# 7_seg.net
KiCad netlist of a schematic drawn in Altium Designer
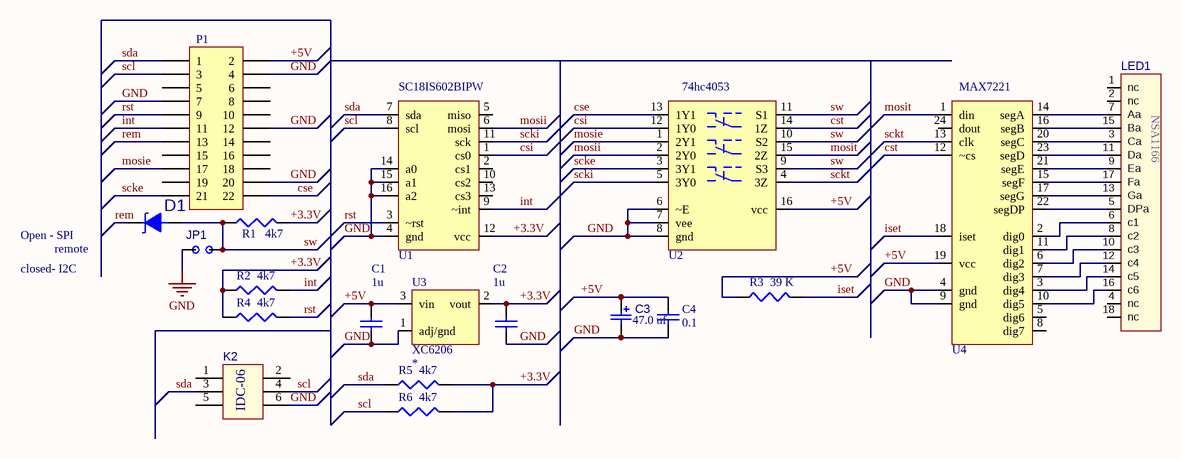
[diagram p0: 7_seg.SchDoc]

(export (version "E")
  (design (tool "Eeschema 10.0.6"))
  (components
    (comp (ref "C1")
      (value "1u")
      (footprint "SM0805")
      (description "Capacitor")
      (fields (field (name "Comment") "cap0805") (field (name "PUBLISHER") "Altium Limited"))
      (libsource (lib "alt2017") (part "cap0805"))
    )
    (comp (ref "C2")
      (value "1u")
      (footprint "SM0805")
      (description "Capacitor")
      (fields (field (name "Comment") "cap0805") (field (name "PUBLISHER") "Altium Limited"))
      (libsource (lib "alt2017") (part "cap0805"))
    )
    (comp (ref "C3")
      (value "CAP_POL_SMB")
      (footprint "CAP_POL_SMB (3528)")
      (description "CAP_POL_SMB(3528)")
      (fields (field (name "ALTIUM_UNNAMED_1") "47.0 uf"))
      (libsource (lib "alt2017") (part "CAP_POL_SMB"))
    )
    (comp (ref "C4")
      (value "0.1")
      (footprint "SM0805")
      (description "Capacitor")
      (fields (field (name "Comment") "cap0805") (field (name "PUBLISHER") "Altium Limited"))
      (libsource (lib "alt2017") (part "cap0805"))
    )
    (comp (ref "D1")
      (value "DiodeShottky_SOD323")
      (footprint "SOD323")
      (description "SOD323")
      (libsource (lib "alt2017") (part "DiodeShottky_SOD323"))
    )
    (comp (ref "JP1") (value "JUMPER2") (footprint "JUMPER2") (libsource (lib "alt2017") (part "JUMPER2")))
    (comp (ref "K2") (value "IDC-06") (footprint "IDC-06") (libsource (lib "alt2017") (part "IDC-06")))
    (comp (ref "LED1")
      (value "NSA1166")
      (footprint "NSA1166")
      (description "NSA retro 7 seg display")
      (libsource (lib "alt2017") (part "NSA1166"))
    )
    (comp (ref "P1")
      (value "2x11,2.54mm vertical")
      (footprint "PLD-22 ,2x11 ,2.54 mm pitch")
      (description "Header, 22-Pin")
      (fields (field (name "PUBLISHER") "Altium Limited"))
      (libsource (lib "alt2017") (part "2x11, 2.54mm, vertical"))
    )
    (comp (ref "R1")
      (value "4k7")
      (footprint "SM0805")
      (description "Resistor")
      (fields (field (name "Comment") "res0805") (field (name "PUBLISHER") "Altium Limited"))
      (libsource (lib "alt2017") (part "res0805"))
    )
    (comp (ref "R2")
      (value "4k7")
      (footprint "SM0805")
      (description "Resistor")
      (fields (field (name "Comment") "res0805") (field (name "PUBLISHER") "Altium Limited"))
      (libsource (lib "alt2017") (part "res0805"))
    )
    (comp (ref "R3")
      (value "39 K")
      (footprint "SM0805")
      (description "Resistor")
      (fields (field (name "Comment") "res0805") (field (name "PUBLISHER") "Altium Limited"))
      (libsource (lib "alt2017") (part "res0805"))
    )
    (comp (ref "R4")
      (value "4k7")
      (footprint "SM0805")
      (description "Resistor")
      (fields (field (name "Comment") "res0805") (field (name "PUBLISHER") "Altium Limited"))
      (libsource (lib "alt2017") (part "res0805"))
    )
    (comp (ref "R5")
      (value "4k7")
      (footprint "SM0805")
      (description "Resistor")
      (fields (field (name "Comment") "res0805") (field (name "PUBLISHER") "Altium Limited"))
      (libsource (lib "alt2017") (part "res0805"))
    )
    (comp (ref "R6")
      (value "4k7")
      (footprint "SM0805")
      (description "Resistor")
      (fields (field (name "Comment") "res0805") (field (name "PUBLISHER") "Altium Limited"))
      (libsource (lib "alt2017") (part "res0805"))
    )
    (comp (ref "U1")
      (value "SC18IS602BIPW")
      (footprint "SSOP16_body_4.5mm")
      (description "i2c to SPI bridge")
      (libsource (lib "alt2017") (part "SC18IS602BIPW"))
    )
    (comp (ref "U2")
      (value "74hc4053")
      (footprint "SSOP16_body_4.5mm")
      (description "3 independent SPDT CMOS switch")
      (libsource (lib "alt2017") (part "74hc4053"))
    )
    (comp (ref "U3")
      (value "XC6206")
      (footprint "SOT-23")
      (description "SOT-23-3 ldo")
      (fields (field (name "ALTIUM_UNNAMED_1") "*"))
      (libsource (lib "alt2017") (part "XC6206"))
    )
    (comp (ref "U4")
      (value "MAX7221")
      (footprint "WSOIC_24_body_7.5mm")
      (description "7 seg 8 digits driver")
      (libsource (lib "alt2017") (part "MAX7221_WSOIC24"))
    )
  )
  (nets
    (net (code "1") (name "/+3.3V") (class "Default")
      (node (ref "C2") (pin "2") (pinfunction "2_2") (pintype "passive"))
      (node (ref "R1") (pin "2") (pinfunction "2_2") (pintype "passive"))
      (node (ref "R2") (pin "1") (pinfunction "1_1") (pintype "passive"))
      (node (ref "R4") (pin "1") (pinfunction "1_1") (pintype "passive"))
      (node (ref "R5") (pin "2") (pinfunction "2_2") (pintype "passive"))
      (node (ref "R6") (pin "2") (pinfunction "2_2") (pintype "passive"))
      (node (ref "U1") (pin "12") (pinfunction "vcc_12") (pintype "passive"))
      (node (ref "U3") (pin "2") (pinfunction "vout_2") (pintype "passive"))
    )
    (net (code "2") (name "/+5V") (class "Default")
      (node (ref "C1") (pin "2") (pinfunction "2_2") (pintype "passive"))
      (node (ref "C3") (pin "1") (pinfunction "a_1") (pintype "passive"))
      (node (ref "C4") (pin "1") (pinfunction "1_1") (pintype "passive"))
      (node (ref "P1") (pin "2") (pinfunction "2_2") (pintype "passive"))
      (node (ref "R3") (pin "1") (pinfunction "1_1") (pintype "passive"))
      (node (ref "U2") (pin "16") (pinfunction "vcc_16") (pintype "passive"))
      (node (ref "U3") (pin "3") (pinfunction "vin_3") (pintype "passive"))
      (node (ref "U4") (pin "19") (pinfunction "vcc_19") (pintype "passive"))
    )
    (net (code "3") (name "/cse") (class "Default")
      (node (ref "P1") (pin "22") (pinfunction "22_22") (pintype "passive"))
      (node (ref "U2") (pin "13") (pinfunction "1Y1_13") (pintype "passive"))
    )
    (net (code "4") (name "/csi") (class "Default")
      (node (ref "U1") (pin "1") (pinfunction "cs0_1") (pintype "passive"))
      (node (ref "U2") (pin "12") (pinfunction "1Y0_12") (pintype "passive"))
    )
    (net (code "5") (name "/cst") (class "Default")
      (node (ref "U2") (pin "14") (pinfunction "1Z_14") (pintype "passive"))
      (node (ref "U4") (pin "12") (pinfunction "~cs_12") (pintype "passive"))
    )
    (net (code "6") (name "/int") (class "Default")
      (node (ref "P1") (pin "11") (pinfunction "11_11") (pintype "passive"))
      (node (ref "R2") (pin "2") (pinfunction "2_2") (pintype "passive"))
      (node (ref "U1") (pin "9") (pinfunction "~int_9") (pintype "passive"))
    )
    (net (code "7") (name "/iset") (class "Default")
      (node (ref "R3") (pin "2") (pinfunction "2_2") (pintype "passive"))
      (node (ref "U4") (pin "18") (pinfunction "iset_18") (pintype "passive"))
    )
    (net (code "8") (name "/mosie") (class "Default")
      (node (ref "P1") (pin "17") (pinfunction "17_17") (pintype "passive"))
      (node (ref "U2") (pin "1") (pinfunction "2Y1_1") (pintype "passive"))
    )
    (net (code "9") (name "/mosii") (class "Default")
      (node (ref "U1") (pin "6") (pinfunction "mosi_6") (pintype "passive"))
      (node (ref "U2") (pin "2") (pinfunction "2Y0_2") (pintype "passive"))
    )
    (net (code "10") (name "/mosit") (class "Default")
      (node (ref "U2") (pin "15") (pinfunction "2Z_15") (pintype "passive"))
      (node (ref "U4") (pin "1") (pinfunction "din_1") (pintype "passive"))
    )
    (net (code "11") (name "/rem") (class "Default")
      (node (ref "D1") (pin "2") (pinfunction "k_2") (pintype "passive"))
      (node (ref "P1") (pin "13") (pinfunction "13_13") (pintype "passive"))
    )
    (net (code "12") (name "/rst") (class "Default")
      (node (ref "P1") (pin "9") (pinfunction "9_9") (pintype "passive"))
      (node (ref "R4") (pin "2") (pinfunction "2_2") (pintype "passive"))
      (node (ref "U1") (pin "3") (pinfunction "~rst_3") (pintype "passive"))
    )
    (net (code "13") (name "/scke") (class "Default")
      (node (ref "P1") (pin "21") (pinfunction "21_21") (pintype "passive"))
      (node (ref "U2") (pin "3") (pinfunction "3Y1_3") (pintype "passive"))
    )
    (net (code "14") (name "/scki") (class "Default")
      (node (ref "U1") (pin "11") (pinfunction "sck_11") (pintype "passive"))
      (node (ref "U2") (pin "5") (pinfunction "3Y0_5") (pintype "passive"))
    )
    (net (code "15") (name "/sckt") (class "Default")
      (node (ref "U2") (pin "4") (pinfunction "3Z_4") (pintype "passive"))
      (node (ref "U4") (pin "13") (pinfunction "clk_13") (pintype "passive"))
    )
    (net (code "16") (name "/scl") (class "Default")
      (node (ref "K2") (pin "4") (pintype "passive"))
      (node (ref "P1") (pin "3") (pinfunction "3_3") (pintype "passive"))
      (node (ref "R6") (pin "1") (pinfunction "1_1") (pintype "passive"))
      (node (ref "U1") (pin "8") (pinfunction "scl_8") (pintype "passive"))
    )
    (net (code "17") (name "/sda") (class "Default")
      (node (ref "K2") (pin "3") (pintype "passive"))
      (node (ref "P1") (pin "1") (pinfunction "1_1") (pintype "passive"))
      (node (ref "R5") (pin "1") (pinfunction "1_1") (pintype "passive"))
      (node (ref "U1") (pin "7") (pinfunction "sda_7") (pintype "passive"))
    )
    (net (code "18") (name "/sw") (class "Default")
      (node (ref "D1") (pin "1") (pinfunction "a_1") (pintype "passive"))
      (node (ref "JP1") (pin "1") (pinfunction "1_1") (pintype "passive"))
      (node (ref "R1") (pin "1") (pinfunction "1_1") (pintype "passive"))
      (node (ref "U2") (pin "10") (pinfunction "S2_10") (pintype "passive"))
      (node (ref "U2") (pin "11") (pinfunction "S1_11") (pintype "passive"))
      (node (ref "U2") (pin "9") (pinfunction "S3_9") (pintype "passive"))
    )
    (net (code "19") (name "GND") (class "Default")
      (node (ref "C1") (pin "1") (pinfunction "1_1") (pintype "passive"))
      (node (ref "C2") (pin "1") (pinfunction "1_1") (pintype "passive"))
      (node (ref "C3") (pin "2") (pinfunction "b_2") (pintype "passive"))
      (node (ref "C4") (pin "2") (pinfunction "2_2") (pintype "passive"))
      (node (ref "JP1") (pin "2") (pinfunction "2_2") (pintype "passive"))
      (node (ref "K2") (pin "6") (pintype "passive"))
      (node (ref "P1") (pin "12") (pinfunction "12_12") (pintype "passive"))
      (node (ref "P1") (pin "20") (pinfunction "20_20") (pintype "passive"))
      (node (ref "P1") (pin "4") (pinfunction "4_4") (pintype "passive"))
      (node (ref "P1") (pin "7") (pinfunction "7_7") (pintype "passive"))
      (node (ref "U1") (pin "14") (pinfunction "a0_14") (pintype "passive"))
      (node (ref "U1") (pin "15") (pinfunction "a1_15") (pintype "passive"))
      (node (ref "U1") (pin "16") (pinfunction "a2_16") (pintype "passive"))
      (node (ref "U1") (pin "4") (pinfunction "gnd_4") (pintype "passive"))
      (node (ref "U2") (pin "6") (pinfunction "~E_6") (pintype "passive"))
      (node (ref "U2") (pin "7") (pinfunction "vee_7") (pintype "passive"))
      (node (ref "U2") (pin "8") (pinfunction "gnd_8") (pintype "passive"))
      (node (ref "U3") (pin "1") (pinfunction "adj/gnd_1") (pintype "passive"))
      (node (ref "U4") (pin "4") (pinfunction "gnd_4") (pintype "passive"))
      (node (ref "U4") (pin "9") (pinfunction "gnd_9") (pintype "passive"))
    )
    (net (code "20") (name "Net-(LED1-Aa)") (class "Default")
      (node (ref "LED1") (pin "7") (pinfunction "Aa_7") (pintype "passive"))
      (node (ref "U4") (pin "14") (pinfunction "segA_14") (pintype "passive"))
    )
    (net (code "21") (name "Net-(LED1-Ba)") (class "Default")
      (node (ref "LED1") (pin "15") (pinfunction "Ba_15") (pintype "passive"))
      (node (ref "U4") (pin "16") (pinfunction "segB_16") (pintype "passive"))
    )
    (net (code "22") (name "Net-(LED1-Ca)") (class "Default")
      (node (ref "LED1") (pin "3") (pinfunction "Ca_3") (pintype "passive"))
      (node (ref "U4") (pin "20") (pinfunction "segC_20") (pintype "passive"))
    )
    (net (code "23") (name "Net-(LED1-DPa)") (class "Default")
      (node (ref "LED1") (pin "5") (pinfunction "DPa_5") (pintype "passive"))
      (node (ref "U4") (pin "22") (pinfunction "segDP_22") (pintype "passive"))
    )
    (net (code "24") (name "Net-(LED1-Da)") (class "Default")
      (node (ref "LED1") (pin "11") (pinfunction "Da_11") (pintype "passive"))
      (node (ref "U4") (pin "23") (pinfunction "segD_23") (pintype "passive"))
    )
    (net (code "25") (name "Net-(LED1-Ea)") (class "Default")
      (node (ref "LED1") (pin "9") (pinfunction "Ea_9") (pintype "passive"))
      (node (ref "U4") (pin "21") (pinfunction "segE_21") (pintype "passive"))
    )
    (net (code "26") (name "Net-(LED1-Fa)") (class "Default")
      (node (ref "LED1") (pin "17") (pinfunction "Fa_17") (pintype "passive"))
      (node (ref "U4") (pin "15") (pinfunction "segF_15") (pintype "passive"))
    )
    (net (code "27") (name "Net-(LED1-Ga)") (class "Default")
      (node (ref "LED1") (pin "13") (pinfunction "Ga_13") (pintype "passive"))
      (node (ref "U4") (pin "17") (pinfunction "segG_17") (pintype "passive"))
    )
    (net (code "28") (name "Net-(LED1-c1)") (class "Default")
      (node (ref "LED1") (pin "6") (pinfunction "c1_6") (pintype "passive"))
      (node (ref "U4") (pin "2") (pinfunction "dig0_2") (pintype "passive"))
    )
    (net (code "29") (name "Net-(LED1-c2)") (class "Default")
      (node (ref "LED1") (pin "8") (pinfunction "c2_8") (pintype "passive"))
      (node (ref "U4") (pin "11") (pinfunction "dig1_11") (pintype "passive"))
    )
    (net (code "30") (name "Net-(LED1-c3)") (class "Default")
      (node (ref "LED1") (pin "10") (pinfunction "c3_10") (pintype "passive"))
      (node (ref "U4") (pin "6") (pinfunction "dig2_6") (pintype "passive"))
    )
    (net (code "31") (name "Net-(LED1-c4)") (class "Default")
      (node (ref "LED1") (pin "12") (pinfunction "c4_12") (pintype "passive"))
      (node (ref "U4") (pin "7") (pinfunction "dig3_7") (pintype "passive"))
    )
    (net (code "32") (name "Net-(LED1-c5)") (class "Default")
      (node (ref "LED1") (pin "14") (pinfunction "c5_14") (pintype "passive"))
      (node (ref "U4") (pin "3") (pinfunction "dig4_3") (pintype "passive"))
    )
    (net (code "33") (name "Net-(LED1-c6)") (class "Default")
      (node (ref "LED1") (pin "16") (pinfunction "c6_16") (pintype "passive"))
      (node (ref "U4") (pin "10") (pinfunction "dig5_10") (pintype "passive"))
    )
    (net (code "34") (name "unconnected-(K2-Pad1)") (class "Default")
      (node (ref "K2") (pin "1") (pintype "passive"))
    )
    (net (code "35") (name "unconnected-(K2-Pad2)") (class "Default")
      (node (ref "K2") (pin "2") (pintype "passive"))
    )
    (net (code "36") (name "unconnected-(K2-Pad5)") (class "Default")
      (node (ref "K2") (pin "5") (pintype "passive"))
    )
    (net (code "37") (name "unconnected-(LED1-nc-Pad1)") (class "Default")
      (node (ref "LED1") (pin "1") (pinfunction "nc_1") (pintype "passive"))
    )
    (net (code "38") (name "unconnected-(LED1-nc-Pad2)") (class "Default")
      (node (ref "LED1") (pin "2") (pinfunction "nc_2") (pintype "passive"))
    )
    (net (code "39") (name "unconnected-(LED1-nc-Pad4)") (class "Default")
      (node (ref "LED1") (pin "4") (pinfunction "nc_4") (pintype "passive"))
    )
    (net (code "40") (name "unconnected-(LED1-nc-Pad18)") (class "Default")
      (node (ref "LED1") (pin "18") (pinfunction "nc_18") (pintype "passive"))
    )
    (net (code "41") (name "unconnected-(P1-Pad5)") (class "Default")
      (node (ref "P1") (pin "5") (pinfunction "5_5") (pintype "passive"))
    )
    (net (code "42") (name "unconnected-(P1-Pad6)") (class "Default")
      (node (ref "P1") (pin "6") (pinfunction "6_6") (pintype "passive"))
    )
    (net (code "43") (name "unconnected-(P1-Pad8)") (class "Default")
      (node (ref "P1") (pin "8") (pinfunction "8_8") (pintype "passive"))
    )
    (net (code "44") (name "unconnected-(P1-Pad10)") (class "Default")
      (node (ref "P1") (pin "10") (pinfunction "10_10") (pintype "passive"))
    )
    (net (code "45") (name "unconnected-(P1-Pad14)") (class "Default")
      (node (ref "P1") (pin "14") (pinfunction "14_14") (pintype "passive"))
    )
    (net (code "46") (name "unconnected-(P1-Pad15)") (class "Default")
      (node (ref "P1") (pin "15") (pinfunction "15_15") (pintype "passive"))
    )
    (net (code "47") (name "unconnected-(P1-Pad16)") (class "Default")
      (node (ref "P1") (pin "16") (pinfunction "16_16") (pintype "passive"))
    )
    (net (code "48") (name "unconnected-(P1-Pad18)") (class "Default")
      (node (ref "P1") (pin "18") (pinfunction "18_18") (pintype "passive"))
    )
    (net (code "49") (name "unconnected-(P1-Pad19)") (class "Default")
      (node (ref "P1") (pin "19") (pinfunction "19_19") (pintype "passive"))
    )
    (net (code "50") (name "unconnected-(U1-cs1-Pad2)") (class "Default")
      (node (ref "U1") (pin "2") (pinfunction "cs1_2") (pintype "passive"))
    )
    (net (code "51") (name "unconnected-(U1-cs2-Pad10)") (class "Default")
      (node (ref "U1") (pin "10") (pinfunction "cs2_10") (pintype "passive"))
    )
    (net (code "52") (name "unconnected-(U1-cs3-Pad13)") (class "Default")
      (node (ref "U1") (pin "13") (pinfunction "cs3_13") (pintype "passive"))
    )
    (net (code "53") (name "unconnected-(U1-miso-Pad5)") (class "Default")
      (node (ref "U1") (pin "5") (pinfunction "miso_5") (pintype "passive"))
    )
    (net (code "54") (name "unconnected-(U4-dig6-Pad5)") (class "Default")
      (node (ref "U4") (pin "5") (pinfunction "dig6_5") (pintype "passive"))
    )
    (net (code "55") (name "unconnected-(U4-dig7-Pad8)") (class "Default")
      (node (ref "U4") (pin "8") (pinfunction "dig7_8") (pintype "passive"))
    )
    (net (code "56") (name "unconnected-(U4-dout-Pad24)") (class "Default")
      (node (ref "U4") (pin "24") (pinfunction "dout_24") (pintype "passive"))
    )
  )
)
